# C-Link.net
KiCad netlist of a schematic drawn in Altium Designer
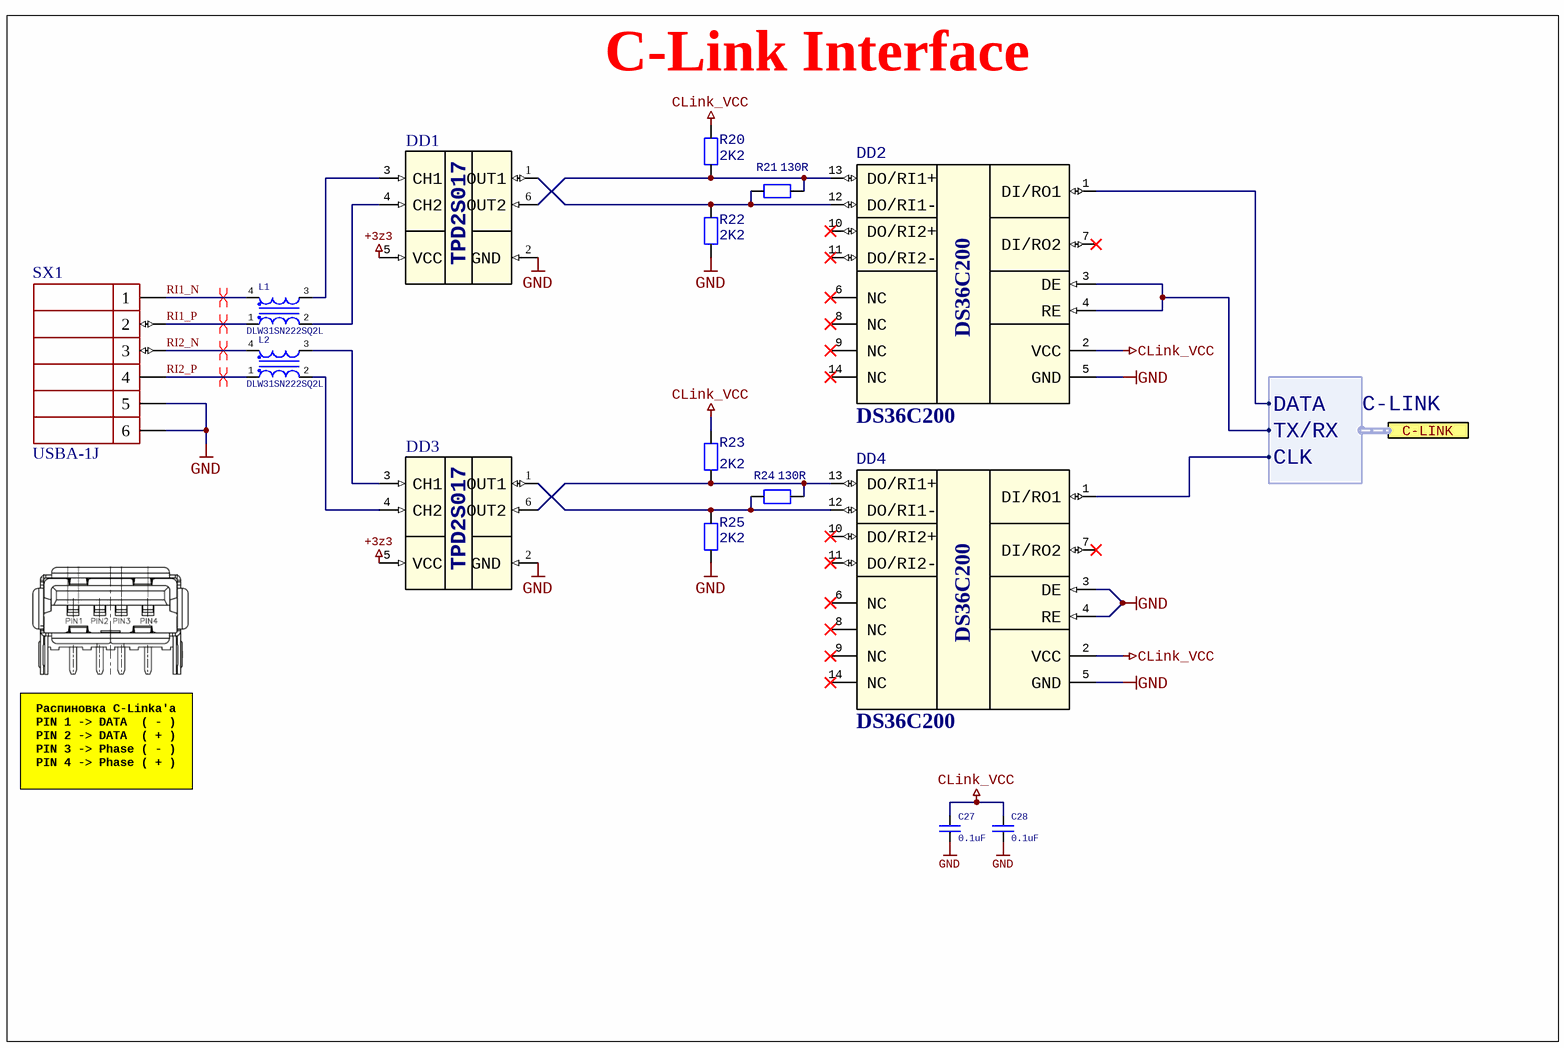
[diagram p0: C-Link.SchDoc]

(export (version "E")
  (design (tool "Eeschema 10.0.6"))
  (components
    (comp (ref "C27")
      (value "0.1uF")
      (footprint "Passive:C_0603")
      (description "Non-polarised capacitor")
      (libsource (lib "Passive") (part "C"))
    )
    (comp (ref "C28")
      (value "0.1uF")
      (footprint "Passive:C_0603")
      (description "Non-polarised capacitor")
      (libsource (lib "Passive") (part "C"))
    )
    (comp (ref "DD1")
      (value "TPD2S017")
      (footprint "SOT:SOT-23-6")
      (libsource (lib "Device") (part "TPD2S017"))
    )
    (comp (ref "DD2") (value "DS36C200") (footprint "SOIC-14") (libsource (lib "Device") (part "DS36C200")))
    (comp (ref "DD3")
      (value "TPD2S017")
      (footprint "SOT:SOT-23-6")
      (libsource (lib "Device") (part "TPD2S017"))
    )
    (comp (ref "DD4") (value "DS36C200") (footprint "SOIC-14") (libsource (lib "Device") (part "DS36C200")))
    (comp (ref "L1")
      (value "DLW31SN222SQ2L")
      (footprint "Choke_Coil")
      (libsource (lib "Passive") (part "L_1"))
    )
    (comp (ref "L2")
      (value "DLW31SN222SQ2L")
      (footprint "Choke_Coil")
      (libsource (lib "Passive") (part "L_1"))
    )
    (comp (ref "R20") (value "2K2") (footprint "Passive:R_0603") (libsource (lib "") (part "R_1")))
    (comp (ref "R21") (value "130R") (footprint "Passive:R_0603") (libsource (lib "Passive") (part "R")))
    (comp (ref "R22") (value "2K2") (footprint "Passive:R_0603") (libsource (lib "") (part "R_1")))
    (comp (ref "R23") (value "2K2") (footprint "Passive:R_0603") (libsource (lib "") (part "R_1")))
    (comp (ref "R24") (value "130R") (footprint "Passive:R_0603") (libsource (lib "Passive") (part "R")))
    (comp (ref "R25") (value "2K2") (footprint "Passive:R_0603") (libsource (lib "") (part "R_1")))
    (comp (ref "SX1")
      (value "USBA-1J")
      (footprint "USB_A_(DS1095)")
      (libsource (lib "Connector") (part "USBA-1J"))
    )
  )
  (nets
    (net (code "2") (name "+3z3") (class "Default")
      (node (ref "DD1") (pin "5") (pinfunction "VCC_5") (pintype "input"))
      (node (ref "DD3") (pin "5") (pinfunction "VCC_5") (pintype "input"))
    )
    (net (code "3") (name "/CLK") (class "Default")
      (node (ref "DD4") (pin "1") (pinfunction "DI/RO1_1") (pintype "bidirectional"))
    )
    (net (code "4") (name "/DATA") (class "Default")
      (node (ref "DD2") (pin "1") (pinfunction "DI/RO1_1") (pintype "bidirectional"))
    )
    (net (code "5") (name "/RI1_N") (class "Default")
      (node (ref "L1") (pin "4") (pinfunction "4_4") (pintype "passive"))
      (node (ref "SX1") (pin "1") (pinfunction "1_1") (pintype "passive"))
    )
    (net (code "6") (name "/RI1_P") (class "Default")
      (node (ref "L1") (pin "1") (pinfunction "1_1") (pintype "passive"))
      (node (ref "SX1") (pin "2") (pinfunction "2_2") (pintype "bidirectional"))
    )
    (net (code "7") (name "/RI2_N") (class "Default")
      (node (ref "L2") (pin "4") (pinfunction "4_4") (pintype "passive"))
      (node (ref "SX1") (pin "3") (pinfunction "3_3") (pintype "bidirectional"))
    )
    (net (code "8") (name "/RI2_P") (class "Default")
      (node (ref "L2") (pin "1") (pinfunction "1_1") (pintype "passive"))
      (node (ref "SX1") (pin "4") (pinfunction "4_4") (pintype "passive"))
    )
    (net (code "9") (name "/TX{slash}RX") (class "Default")
      (node (ref "DD2") (pin "3") (pinfunction "DE_3") (pintype "input"))
      (node (ref "DD2") (pin "4") (pinfunction "RE_4") (pintype "input"))
    )
    (net (code "11") (name "CLink_VCC") (class "Default")
      (node (ref "C27") (pin "2") (pinfunction "2_2") (pintype "passive"))
      (node (ref "C28") (pin "2") (pinfunction "2_2") (pintype "passive"))
      (node (ref "DD2") (pin "2") (pinfunction "VCC_2") (pintype "passive"))
      (node (ref "DD4") (pin "2") (pinfunction "VCC_2") (pintype "passive"))
      (node (ref "R20") (pin "1") (pinfunction "1_1") (pintype "passive"))
      (node (ref "R23") (pin "1") (pinfunction "1_1") (pintype "passive"))
    )
    (net (code "12") (name "GND") (class "Default")
      (node (ref "C27") (pin "1") (pinfunction "1_1") (pintype "passive"))
      (node (ref "C28") (pin "1") (pinfunction "1_1") (pintype "passive"))
      (node (ref "DD1") (pin "2") (pinfunction "GND_2") (pintype "input"))
      (node (ref "DD2") (pin "5") (pinfunction "GND_5") (pintype "passive"))
      (node (ref "DD3") (pin "2") (pinfunction "GND_2") (pintype "input"))
      (node (ref "DD4") (pin "3") (pinfunction "DE_3") (pintype "input"))
      (node (ref "DD4") (pin "4") (pinfunction "RE_4") (pintype "input"))
      (node (ref "DD4") (pin "5") (pinfunction "GND_5") (pintype "passive"))
      (node (ref "R22") (pin "2") (pinfunction "2_2") (pintype "passive"))
      (node (ref "R25") (pin "2") (pinfunction "2_2") (pintype "passive"))
      (node (ref "SX1") (pin "5") (pinfunction "5_5") (pintype "passive"))
      (node (ref "SX1") (pin "6") (pinfunction "6_6") (pintype "passive"))
    )
    (net (code "13") (name "Net-(DD1-CH1)") (class "Default")
      (node (ref "DD1") (pin "3") (pinfunction "CH1_3") (pintype "input"))
      (node (ref "L1") (pin "3") (pinfunction "3_3") (pintype "passive"))
    )
    (net (code "14") (name "Net-(DD1-CH2)") (class "Default")
      (node (ref "DD1") (pin "4") (pinfunction "CH2_4") (pintype "input"))
      (node (ref "L1") (pin "2") (pinfunction "2_2") (pintype "passive"))
    )
    (net (code "15") (name "Net-(DD1-OUT1)") (class "Default")
      (node (ref "DD1") (pin "1") (pinfunction "OUT1_1") (pintype "bidirectional"))
      (node (ref "DD2") (pin "12") (pinfunction "DO/RI1-_12") (pintype "bidirectional"))
      (node (ref "R21") (pin "1") (pinfunction "1_1") (pintype "passive"))
      (node (ref "R22") (pin "1") (pinfunction "1_1") (pintype "passive"))
    )
    (net (code "16") (name "Net-(DD1-OUT2)") (class "Default")
      (node (ref "DD1") (pin "6") (pinfunction "OUT2_6") (pintype "input"))
      (node (ref "DD2") (pin "13") (pinfunction "DO/RI1+_13") (pintype "bidirectional"))
      (node (ref "R20") (pin "2") (pinfunction "2_2") (pintype "passive"))
      (node (ref "R21") (pin "2") (pinfunction "2_2") (pintype "passive"))
    )
    (net (code "17") (name "Net-(DD3-CH1)") (class "Default")
      (node (ref "DD3") (pin "3") (pinfunction "CH1_3") (pintype "input"))
      (node (ref "L2") (pin "3") (pinfunction "3_3") (pintype "passive"))
    )
    (net (code "18") (name "Net-(DD3-CH2)") (class "Default")
      (node (ref "DD3") (pin "4") (pinfunction "CH2_4") (pintype "input"))
      (node (ref "L2") (pin "2") (pinfunction "2_2") (pintype "passive"))
    )
    (net (code "19") (name "Net-(DD3-OUT1)") (class "Default")
      (node (ref "DD3") (pin "1") (pinfunction "OUT1_1") (pintype "bidirectional"))
      (node (ref "DD4") (pin "12") (pinfunction "DO/RI1-_12") (pintype "bidirectional"))
      (node (ref "R24") (pin "1") (pinfunction "1_1") (pintype "passive"))
      (node (ref "R25") (pin "1") (pinfunction "1_1") (pintype "passive"))
    )
    (net (code "20") (name "Net-(DD3-OUT2)") (class "Default")
      (node (ref "DD3") (pin "6") (pinfunction "OUT2_6") (pintype "input"))
      (node (ref "DD4") (pin "13") (pinfunction "DO/RI1+_13") (pintype "bidirectional"))
      (node (ref "R23") (pin "2") (pinfunction "2_2") (pintype "passive"))
      (node (ref "R24") (pin "2") (pinfunction "2_2") (pintype "passive"))
    )
    (net (code "21") (name "unconnected-(DD2-DI{slash}RO2-Pad7)") (class "Default")
      (node (ref "DD2") (pin "7") (pinfunction "DI/RO2_7") (pintype "bidirectional+no_connect"))
    )
    (net (code "22") (name "unconnected-(DD2-DO{slash}RI2+-Pad10)") (class "Default")
      (node (ref "DD2") (pin "10") (pinfunction "DO/RI2+_10") (pintype "bidirectional+no_connect"))
    )
    (net (code "23") (name "unconnected-(DD2-DO{slash}RI2--Pad11)") (class "Default")
      (node (ref "DD2") (pin "11") (pinfunction "DO/RI2-_11") (pintype "bidirectional+no_connect"))
    )
    (net (code "24") (name "unconnected-(DD2-NC-Pad6)") (class "Default")
      (node (ref "DD2") (pin "6") (pinfunction "NC_6") (pintype "passive+no_connect"))
    )
    (net (code "25") (name "unconnected-(DD2-NC-Pad8)") (class "Default")
      (node (ref "DD2") (pin "8") (pinfunction "NC_8") (pintype "passive+no_connect"))
    )
    (net (code "26") (name "unconnected-(DD2-NC-Pad9)") (class "Default")
      (node (ref "DD2") (pin "9") (pinfunction "NC_9") (pintype "passive+no_connect"))
    )
    (net (code "27") (name "unconnected-(DD2-NC-Pad14)") (class "Default")
      (node (ref "DD2") (pin "14") (pinfunction "NC_14") (pintype "passive+no_connect"))
    )
    (net (code "28") (name "unconnected-(DD4-DI{slash}RO2-Pad7)") (class "Default")
      (node (ref "DD4") (pin "7") (pinfunction "DI/RO2_7") (pintype "bidirectional+no_connect"))
    )
    (net (code "29") (name "unconnected-(DD4-DO{slash}RI2+-Pad10)") (class "Default")
      (node (ref "DD4") (pin "10") (pinfunction "DO/RI2+_10") (pintype "bidirectional+no_connect"))
    )
    (net (code "30") (name "unconnected-(DD4-DO{slash}RI2--Pad11)") (class "Default")
      (node (ref "DD4") (pin "11") (pinfunction "DO/RI2-_11") (pintype "bidirectional+no_connect"))
    )
    (net (code "31") (name "unconnected-(DD4-NC-Pad6)") (class "Default")
      (node (ref "DD4") (pin "6") (pinfunction "NC_6") (pintype "passive+no_connect"))
    )
    (net (code "32") (name "unconnected-(DD4-NC-Pad8)") (class "Default")
      (node (ref "DD4") (pin "8") (pinfunction "NC_8") (pintype "passive+no_connect"))
    )
    (net (code "33") (name "unconnected-(DD4-NC-Pad9)") (class "Default")
      (node (ref "DD4") (pin "9") (pinfunction "NC_9") (pintype "passive+no_connect"))
    )
    (net (code "34") (name "unconnected-(DD4-NC-Pad14)") (class "Default")
      (node (ref "DD4") (pin "14") (pinfunction "NC_14") (pintype "passive+no_connect"))
    )
  )
)
